# BoardConnectors.net
KiCad netlist of a schematic drawn in Altium Designer
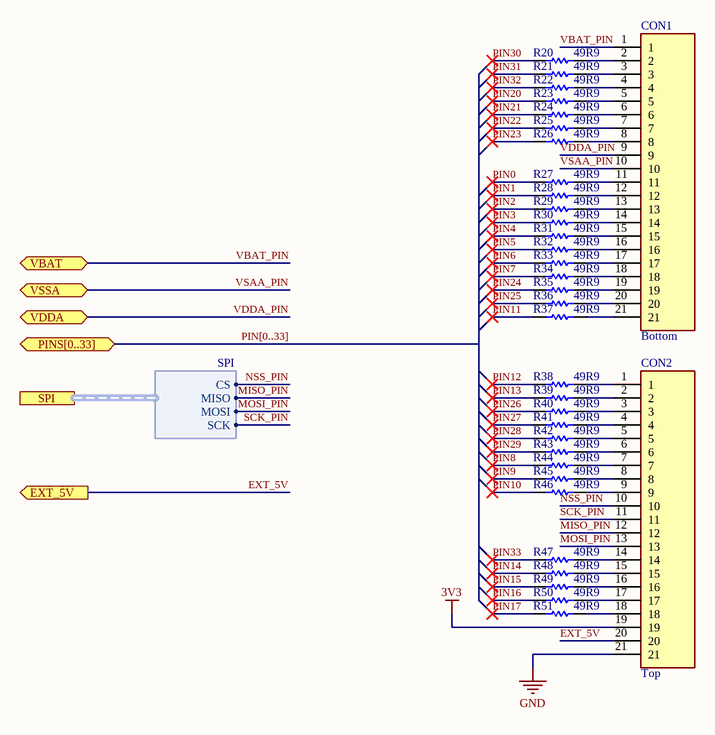
[diagram p0: BoardConnectors.SchDoc]

(export (version "E")
  (design (tool "Eeschema 10.0.6"))
  (components
    (comp (ref "CON1")
      (value "Header 21")
      (footprint "HDR_1X21_2.54")
      (description "Connector")
      (fields
        (field (name "MPN") "68001-121HLF")
        (field (name "MOUSER PART NUMBER") "649-68001-121HLF")
        (field (name "LOCATION") "Bottom")
      )
      (libsource (lib "Library") (part "Header 21"))
    )
    (comp (ref "CON2")
      (value "Header 21")
      (footprint "HDR_1X21_2.54")
      (description "Connector")
      (fields
        (field (name "MPN") "68001-121HLF")
        (field (name "MOUSER PART NUMBER") "649-68001-121HLF")
        (field (name "LOCATION") "Top")
      )
      (libsource (lib "Library") (part "Header 21"))
    )
    (comp (ref "R20")
      (value "49R9")
      (footprint "Res_0603_MD")
      (description "Resistor")
      (fields (field (name "MPN") "CRCW060349R9FKEA"))
      (libsource (lib "LibPassive") (part "Resistor"))
    )
    (comp (ref "R21")
      (value "49R9")
      (footprint "Res_0603_MD")
      (description "Resistor")
      (fields (field (name "MPN") "CRCW060349R9FKEA"))
      (libsource (lib "LibPassive") (part "Resistor"))
    )
    (comp (ref "R22")
      (value "49R9")
      (footprint "Res_0603_MD")
      (description "Resistor")
      (fields (field (name "MPN") "CRCW060349R9FKEA"))
      (libsource (lib "LibPassive") (part "Resistor"))
    )
    (comp (ref "R23")
      (value "49R9")
      (footprint "Res_0603_MD")
      (description "Resistor")
      (fields (field (name "MPN") "CRCW060349R9FKEA"))
      (libsource (lib "LibPassive") (part "Resistor"))
    )
    (comp (ref "R24")
      (value "49R9")
      (footprint "Res_0603_MD")
      (description "Resistor")
      (fields (field (name "MPN") "CRCW060349R9FKEA"))
      (libsource (lib "LibPassive") (part "Resistor"))
    )
    (comp (ref "R25")
      (value "49R9")
      (footprint "Res_0603_MD")
      (description "Resistor")
      (fields (field (name "MPN") "CRCW060349R9FKEA"))
      (libsource (lib "LibPassive") (part "Resistor"))
    )
    (comp (ref "R26")
      (value "49R9")
      (footprint "Res_0603_MD")
      (description "Resistor")
      (fields (field (name "MPN") "CRCW060349R9FKEA"))
      (libsource (lib "LibPassive") (part "Resistor"))
    )
    (comp (ref "R27")
      (value "49R9")
      (footprint "Res_0603_MD")
      (description "Resistor")
      (fields (field (name "MPN") "CRCW060349R9FKEA"))
      (libsource (lib "LibPassive") (part "Resistor"))
    )
    (comp (ref "R28")
      (value "49R9")
      (footprint "Res_0603_MD")
      (description "Resistor")
      (fields (field (name "MPN") "CRCW060349R9FKEA"))
      (libsource (lib "LibPassive") (part "Resistor"))
    )
    (comp (ref "R29")
      (value "49R9")
      (footprint "Res_0603_MD")
      (description "Resistor")
      (fields (field (name "MPN") "CRCW060349R9FKEA"))
      (libsource (lib "LibPassive") (part "Resistor"))
    )
    (comp (ref "R30")
      (value "49R9")
      (footprint "Res_0603_MD")
      (description "Resistor")
      (fields (field (name "MPN") "CRCW060349R9FKEA"))
      (libsource (lib "LibPassive") (part "Resistor"))
    )
    (comp (ref "R31")
      (value "49R9")
      (footprint "Res_0603_MD")
      (description "Resistor")
      (fields (field (name "MPN") "CRCW060349R9FKEA"))
      (libsource (lib "LibPassive") (part "Resistor"))
    )
    (comp (ref "R32")
      (value "49R9")
      (footprint "Res_0603_MD")
      (description "Resistor")
      (fields (field (name "MPN") "CRCW060349R9FKEA"))
      (libsource (lib "LibPassive") (part "Resistor"))
    )
    (comp (ref "R33")
      (value "49R9")
      (footprint "Res_0603_MD")
      (description "Resistor")
      (fields (field (name "MPN") "CRCW060349R9FKEA"))
      (libsource (lib "LibPassive") (part "Resistor"))
    )
    (comp (ref "R34")
      (value "49R9")
      (footprint "Res_0603_MD")
      (description "Resistor")
      (fields (field (name "MPN") "CRCW060349R9FKEA"))
      (libsource (lib "LibPassive") (part "Resistor"))
    )
    (comp (ref "R35")
      (value "49R9")
      (footprint "Res_0603_MD")
      (description "Resistor")
      (fields (field (name "MPN") "CRCW060349R9FKEA"))
      (libsource (lib "LibPassive") (part "Resistor"))
    )
    (comp (ref "R36")
      (value "49R9")
      (footprint "Res_0603_MD")
      (description "Resistor")
      (fields (field (name "MPN") "CRCW060349R9FKEA"))
      (libsource (lib "LibPassive") (part "Resistor"))
    )
    (comp (ref "R37")
      (value "49R9")
      (footprint "Res_0603_MD")
      (description "Resistor")
      (fields (field (name "MPN") "CRCW060349R9FKEA"))
      (libsource (lib "LibPassive") (part "Resistor"))
    )
    (comp (ref "R38")
      (value "49R9")
      (footprint "Res_0603_MD")
      (description "Resistor")
      (fields (field (name "MPN") "CRCW060349R9FKEA"))
      (libsource (lib "LibPassive") (part "Resistor"))
    )
    (comp (ref "R39")
      (value "49R9")
      (footprint "Res_0603_MD")
      (description "Resistor")
      (fields (field (name "MPN") "CRCW060349R9FKEA"))
      (libsource (lib "LibPassive") (part "Resistor"))
    )
    (comp (ref "R40")
      (value "49R9")
      (footprint "Res_0603_MD")
      (description "Resistor")
      (fields (field (name "MPN") "CRCW060349R9FKEA"))
      (libsource (lib "LibPassive") (part "Resistor"))
    )
    (comp (ref "R41")
      (value "49R9")
      (footprint "Res_0603_MD")
      (description "Resistor")
      (fields (field (name "MPN") "CRCW060349R9FKEA"))
      (libsource (lib "LibPassive") (part "Resistor"))
    )
    (comp (ref "R42")
      (value "49R9")
      (footprint "Res_0603_MD")
      (description "Resistor")
      (fields (field (name "MPN") "CRCW060349R9FKEA"))
      (libsource (lib "LibPassive") (part "Resistor"))
    )
    (comp (ref "R43")
      (value "49R9")
      (footprint "Res_0603_MD")
      (description "Resistor")
      (fields (field (name "MPN") "CRCW060349R9FKEA"))
      (libsource (lib "LibPassive") (part "Resistor"))
    )
    (comp (ref "R44")
      (value "49R9")
      (footprint "Res_0603_MD")
      (description "Resistor")
      (fields (field (name "MPN") "CRCW060349R9FKEA"))
      (libsource (lib "LibPassive") (part "Resistor"))
    )
    (comp (ref "R45")
      (value "49R9")
      (footprint "Res_0603_MD")
      (description "Resistor")
      (fields (field (name "MPN") "CRCW060349R9FKEA"))
      (libsource (lib "LibPassive") (part "Resistor"))
    )
    (comp (ref "R46")
      (value "49R9")
      (footprint "Res_0603_MD")
      (description "Resistor")
      (fields (field (name "MPN") "CRCW060349R9FKEA"))
      (libsource (lib "LibPassive") (part "Resistor"))
    )
    (comp (ref "R47")
      (value "49R9")
      (footprint "Res_0603_MD")
      (description "Resistor")
      (fields (field (name "MPN") "CRCW060349R9FKEA"))
      (libsource (lib "LibPassive") (part "Resistor"))
    )
    (comp (ref "R48")
      (value "49R9")
      (footprint "Res_0603_MD")
      (description "Resistor")
      (fields (field (name "MPN") "CRCW060349R9FKEA"))
      (libsource (lib "LibPassive") (part "Resistor"))
    )
    (comp (ref "R49")
      (value "49R9")
      (footprint "Res_0603_MD")
      (description "Resistor")
      (fields (field (name "MPN") "CRCW060349R9FKEA"))
      (libsource (lib "LibPassive") (part "Resistor"))
    )
    (comp (ref "R50")
      (value "49R9")
      (footprint "Res_0603_MD")
      (description "Resistor")
      (fields (field (name "MPN") "CRCW060349R9FKEA"))
      (libsource (lib "LibPassive") (part "Resistor"))
    )
    (comp (ref "R51")
      (value "49R9")
      (footprint "Res_0603_MD")
      (description "Resistor")
      (fields (field (name "MPN") "CRCW060349R9FKEA"))
      (libsource (lib "LibPassive") (part "Resistor"))
    )
  )
  (nets
    (net (code "4") (name "/EXT_5V") (class "Default")
      (node (ref "CON2") (pin "20") (pinfunction "20_20") (pintype "passive"))
    )
    (net (code "5") (name "/MISO_PIN") (class "Default")
      (node (ref "CON2") (pin "12") (pinfunction "12_12") (pintype "passive"))
    )
    (net (code "6") (name "/MOSI_PIN") (class "Default")
      (node (ref "CON2") (pin "13") (pinfunction "13_13") (pintype "passive"))
    )
    (net (code "7") (name "/NSS_PIN") (class "Default")
      (node (ref "CON2") (pin "10") (pinfunction "10_10") (pintype "passive"))
    )
    (net (code "8") (name "/PIN0") (class "Default")
      (node (ref "R27") (pin "1") (pinfunction "1_1") (pintype "passive+no_connect"))
    )
    (net (code "9") (name "/PIN1") (class "Default")
      (node (ref "R28") (pin "1") (pinfunction "1_1") (pintype "passive+no_connect"))
    )
    (net (code "10") (name "/PIN2") (class "Default")
      (node (ref "R29") (pin "1") (pinfunction "1_1") (pintype "passive+no_connect"))
    )
    (net (code "11") (name "/PIN3") (class "Default")
      (node (ref "R30") (pin "1") (pinfunction "1_1") (pintype "passive+no_connect"))
    )
    (net (code "12") (name "/PIN4") (class "Default")
      (node (ref "R31") (pin "1") (pinfunction "1_1") (pintype "passive+no_connect"))
    )
    (net (code "13") (name "/PIN5") (class "Default")
      (node (ref "R32") (pin "1") (pinfunction "1_1") (pintype "passive+no_connect"))
    )
    (net (code "14") (name "/PIN6") (class "Default")
      (node (ref "R33") (pin "1") (pinfunction "1_1") (pintype "passive+no_connect"))
    )
    (net (code "15") (name "/PIN7") (class "Default")
      (node (ref "R34") (pin "1") (pinfunction "1_1") (pintype "passive+no_connect"))
    )
    (net (code "16") (name "/PIN8") (class "Default")
      (node (ref "R44") (pin "1") (pinfunction "1_1") (pintype "passive+no_connect"))
    )
    (net (code "17") (name "/PIN9") (class "Default")
      (node (ref "R45") (pin "1") (pinfunction "1_1") (pintype "passive+no_connect"))
    )
    (net (code "18") (name "/PIN10") (class "Default")
      (node (ref "R46") (pin "1") (pinfunction "1_1") (pintype "passive+no_connect"))
    )
    (net (code "19") (name "/PIN11") (class "Default")
      (node (ref "R37") (pin "1") (pinfunction "1_1") (pintype "passive+no_connect"))
    )
    (net (code "20") (name "/PIN12") (class "Default")
      (node (ref "R38") (pin "1") (pinfunction "1_1") (pintype "passive+no_connect"))
    )
    (net (code "21") (name "/PIN13") (class "Default")
      (node (ref "R39") (pin "1") (pinfunction "1_1") (pintype "passive+no_connect"))
    )
    (net (code "22") (name "/PIN14") (class "Default")
      (node (ref "R48") (pin "1") (pinfunction "1_1") (pintype "passive+no_connect"))
    )
    (net (code "23") (name "/PIN15") (class "Default")
      (node (ref "R49") (pin "1") (pinfunction "1_1") (pintype "passive+no_connect"))
    )
    (net (code "24") (name "/PIN16") (class "Default")
      (node (ref "R50") (pin "1") (pinfunction "1_1") (pintype "passive+no_connect"))
    )
    (net (code "25") (name "/PIN17") (class "Default")
      (node (ref "R51") (pin "1") (pinfunction "1_1") (pintype "passive+no_connect"))
    )
    (net (code "26") (name "/PIN20") (class "Default")
      (node (ref "R23") (pin "1") (pinfunction "1_1") (pintype "passive+no_connect"))
    )
    (net (code "27") (name "/PIN21") (class "Default")
      (node (ref "R24") (pin "1") (pinfunction "1_1") (pintype "passive+no_connect"))
    )
    (net (code "28") (name "/PIN22") (class "Default")
      (node (ref "R25") (pin "1") (pinfunction "1_1") (pintype "passive+no_connect"))
    )
    (net (code "29") (name "/PIN23") (class "Default")
      (node (ref "R26") (pin "1") (pinfunction "1_1") (pintype "passive+no_connect"))
    )
    (net (code "30") (name "/PIN24") (class "Default")
      (node (ref "R35") (pin "1") (pinfunction "1_1") (pintype "passive+no_connect"))
    )
    (net (code "31") (name "/PIN25") (class "Default")
      (node (ref "R36") (pin "1") (pinfunction "1_1") (pintype "passive+no_connect"))
    )
    (net (code "32") (name "/PIN26") (class "Default")
      (node (ref "R40") (pin "1") (pinfunction "1_1") (pintype "passive+no_connect"))
    )
    (net (code "33") (name "/PIN27") (class "Default")
      (node (ref "R41") (pin "1") (pinfunction "1_1") (pintype "passive+no_connect"))
    )
    (net (code "34") (name "/PIN28") (class "Default")
      (node (ref "R42") (pin "1") (pinfunction "1_1") (pintype "passive+no_connect"))
    )
    (net (code "35") (name "/PIN29") (class "Default")
      (node (ref "R43") (pin "1") (pinfunction "1_1") (pintype "passive+no_connect"))
    )
    (net (code "36") (name "/PIN30") (class "Default")
      (node (ref "R20") (pin "1") (pinfunction "1_1") (pintype "passive+no_connect"))
    )
    (net (code "37") (name "/PIN31") (class "Default")
      (node (ref "R21") (pin "1") (pinfunction "1_1") (pintype "passive+no_connect"))
    )
    (net (code "38") (name "/PIN32") (class "Default")
      (node (ref "R22") (pin "1") (pinfunction "1_1") (pintype "passive+no_connect"))
    )
    (net (code "39") (name "/PIN33") (class "Default")
      (node (ref "R47") (pin "1") (pinfunction "1_1") (pintype "passive+no_connect"))
    )
    (net (code "41") (name "/SCK_PIN") (class "Default")
      (node (ref "CON2") (pin "11") (pinfunction "11_11") (pintype "passive"))
    )
    (net (code "42") (name "/VBAT_PIN") (class "Default")
      (node (ref "CON1") (pin "1") (pinfunction "1_1") (pintype "passive"))
    )
    (net (code "43") (name "/VDDA_PIN") (class "Default")
      (node (ref "CON1") (pin "9") (pinfunction "9_9") (pintype "passive"))
    )
    (net (code "44") (name "/VSAA_PIN") (class "Default")
      (node (ref "CON1") (pin "10") (pinfunction "10_10") (pintype "passive"))
    )
    (net (code "46") (name "3V3") (class "Default")
      (node (ref "CON2") (pin "19") (pinfunction "19_19") (pintype "passive"))
    )
    (net (code "47") (name "GND") (class "Default")
      (node (ref "CON2") (pin "21") (pinfunction "21_21") (pintype "passive"))
    )
    (net (code "48") (name "Net-(CON1-Pad2)") (class "Default")
      (node (ref "CON1") (pin "2") (pinfunction "2_2") (pintype "passive"))
      (node (ref "R20") (pin "2") (pinfunction "2_2") (pintype "passive"))
    )
    (net (code "49") (name "Net-(CON1-Pad3)") (class "Default")
      (node (ref "CON1") (pin "3") (pinfunction "3_3") (pintype "passive"))
      (node (ref "R21") (pin "2") (pinfunction "2_2") (pintype "passive"))
    )
    (net (code "50") (name "Net-(CON1-Pad4)") (class "Default")
      (node (ref "CON1") (pin "4") (pinfunction "4_4") (pintype "passive"))
      (node (ref "R22") (pin "2") (pinfunction "2_2") (pintype "passive"))
    )
    (net (code "51") (name "Net-(CON1-Pad5)") (class "Default")
      (node (ref "CON1") (pin "5") (pinfunction "5_5") (pintype "passive"))
      (node (ref "R23") (pin "2") (pinfunction "2_2") (pintype "passive"))
    )
    (net (code "52") (name "Net-(CON1-Pad6)") (class "Default")
      (node (ref "CON1") (pin "6") (pinfunction "6_6") (pintype "passive"))
      (node (ref "R24") (pin "2") (pinfunction "2_2") (pintype "passive"))
    )
    (net (code "53") (name "Net-(CON1-Pad7)") (class "Default")
      (node (ref "CON1") (pin "7") (pinfunction "7_7") (pintype "passive"))
      (node (ref "R25") (pin "2") (pinfunction "2_2") (pintype "passive"))
    )
    (net (code "54") (name "Net-(CON1-Pad8)") (class "Default")
      (node (ref "CON1") (pin "8") (pinfunction "8_8") (pintype "passive"))
      (node (ref "R26") (pin "2") (pinfunction "2_2") (pintype "passive"))
    )
    (net (code "55") (name "Net-(CON1-Pad11)") (class "Default")
      (node (ref "CON1") (pin "11") (pinfunction "11_11") (pintype "passive"))
      (node (ref "R27") (pin "2") (pinfunction "2_2") (pintype "passive"))
    )
    (net (code "56") (name "Net-(CON1-Pad12)") (class "Default")
      (node (ref "CON1") (pin "12") (pinfunction "12_12") (pintype "passive"))
      (node (ref "R28") (pin "2") (pinfunction "2_2") (pintype "passive"))
    )
    (net (code "57") (name "Net-(CON1-Pad13)") (class "Default")
      (node (ref "CON1") (pin "13") (pinfunction "13_13") (pintype "passive"))
      (node (ref "R29") (pin "2") (pinfunction "2_2") (pintype "passive"))
    )
    (net (code "58") (name "Net-(CON1-Pad14)") (class "Default")
      (node (ref "CON1") (pin "14") (pinfunction "14_14") (pintype "passive"))
      (node (ref "R30") (pin "2") (pinfunction "2_2") (pintype "passive"))
    )
    (net (code "59") (name "Net-(CON1-Pad15)") (class "Default")
      (node (ref "CON1") (pin "15") (pinfunction "15_15") (pintype "passive"))
      (node (ref "R31") (pin "2") (pinfunction "2_2") (pintype "passive"))
    )
    (net (code "60") (name "Net-(CON1-Pad16)") (class "Default")
      (node (ref "CON1") (pin "16") (pinfunction "16_16") (pintype "passive"))
      (node (ref "R32") (pin "2") (pinfunction "2_2") (pintype "passive"))
    )
    (net (code "61") (name "Net-(CON1-Pad17)") (class "Default")
      (node (ref "CON1") (pin "17") (pinfunction "17_17") (pintype "passive"))
      (node (ref "R33") (pin "2") (pinfunction "2_2") (pintype "passive"))
    )
    (net (code "62") (name "Net-(CON1-Pad18)") (class "Default")
      (node (ref "CON1") (pin "18") (pinfunction "18_18") (pintype "passive"))
      (node (ref "R34") (pin "2") (pinfunction "2_2") (pintype "passive"))
    )
    (net (code "63") (name "Net-(CON1-Pad19)") (class "Default")
      (node (ref "CON1") (pin "19") (pinfunction "19_19") (pintype "passive"))
      (node (ref "R35") (pin "2") (pinfunction "2_2") (pintype "passive"))
    )
    (net (code "64") (name "Net-(CON1-Pad20)") (class "Default")
      (node (ref "CON1") (pin "20") (pinfunction "20_20") (pintype "passive"))
      (node (ref "R36") (pin "2") (pinfunction "2_2") (pintype "passive"))
    )
    (net (code "65") (name "Net-(CON1-Pad21)") (class "Default")
      (node (ref "CON1") (pin "21") (pinfunction "21_21") (pintype "passive"))
      (node (ref "R37") (pin "2") (pinfunction "2_2") (pintype "passive"))
    )
    (net (code "66") (name "Net-(CON2-Pad1)") (class "Default")
      (node (ref "CON2") (pin "1") (pinfunction "1_1") (pintype "passive"))
      (node (ref "R38") (pin "2") (pinfunction "2_2") (pintype "passive"))
    )
    (net (code "67") (name "Net-(CON2-Pad2)") (class "Default")
      (node (ref "CON2") (pin "2") (pinfunction "2_2") (pintype "passive"))
      (node (ref "R39") (pin "2") (pinfunction "2_2") (pintype "passive"))
    )
    (net (code "68") (name "Net-(CON2-Pad3)") (class "Default")
      (node (ref "CON2") (pin "3") (pinfunction "3_3") (pintype "passive"))
      (node (ref "R40") (pin "2") (pinfunction "2_2") (pintype "passive"))
    )
    (net (code "69") (name "Net-(CON2-Pad4)") (class "Default")
      (node (ref "CON2") (pin "4") (pinfunction "4_4") (pintype "passive"))
      (node (ref "R41") (pin "2") (pinfunction "2_2") (pintype "passive"))
    )
    (net (code "70") (name "Net-(CON2-Pad5)") (class "Default")
      (node (ref "CON2") (pin "5") (pinfunction "5_5") (pintype "passive"))
      (node (ref "R42") (pin "2") (pinfunction "2_2") (pintype "passive"))
    )
    (net (code "71") (name "Net-(CON2-Pad6)") (class "Default")
      (node (ref "CON2") (pin "6") (pinfunction "6_6") (pintype "passive"))
      (node (ref "R43") (pin "2") (pinfunction "2_2") (pintype "passive"))
    )
    (net (code "72") (name "Net-(CON2-Pad7)") (class "Default")
      (node (ref "CON2") (pin "7") (pinfunction "7_7") (pintype "passive"))
      (node (ref "R44") (pin "2") (pinfunction "2_2") (pintype "passive"))
    )
    (net (code "73") (name "Net-(CON2-Pad8)") (class "Default")
      (node (ref "CON2") (pin "8") (pinfunction "8_8") (pintype "passive"))
      (node (ref "R45") (pin "2") (pinfunction "2_2") (pintype "passive"))
    )
    (net (code "74") (name "Net-(CON2-Pad9)") (class "Default")
      (node (ref "CON2") (pin "9") (pinfunction "9_9") (pintype "passive"))
      (node (ref "R46") (pin "2") (pinfunction "2_2") (pintype "passive"))
    )
    (net (code "75") (name "Net-(CON2-Pad14)") (class "Default")
      (node (ref "CON2") (pin "14") (pinfunction "14_14") (pintype "passive"))
      (node (ref "R47") (pin "2") (pinfunction "2_2") (pintype "passive"))
    )
    (net (code "76") (name "Net-(CON2-Pad15)") (class "Default")
      (node (ref "CON2") (pin "15") (pinfunction "15_15") (pintype "passive"))
      (node (ref "R48") (pin "2") (pinfunction "2_2") (pintype "passive"))
    )
    (net (code "77") (name "Net-(CON2-Pad16)") (class "Default")
      (node (ref "CON2") (pin "16") (pinfunction "16_16") (pintype "passive"))
      (node (ref "R49") (pin "2") (pinfunction "2_2") (pintype "passive"))
    )
    (net (code "78") (name "Net-(CON2-Pad17)") (class "Default")
      (node (ref "CON2") (pin "17") (pinfunction "17_17") (pintype "passive"))
      (node (ref "R50") (pin "2") (pinfunction "2_2") (pintype "passive"))
    )
    (net (code "79") (name "Net-(CON2-Pad18)") (class "Default")
      (node (ref "CON2") (pin "18") (pinfunction "18_18") (pintype "passive"))
      (node (ref "R51") (pin "2") (pinfunction "2_2") (pintype "passive"))
    )
  )
)
